# Telemetry_layoutmainVer3.net
KiCad netlist of a schematic drawn in EAGLE
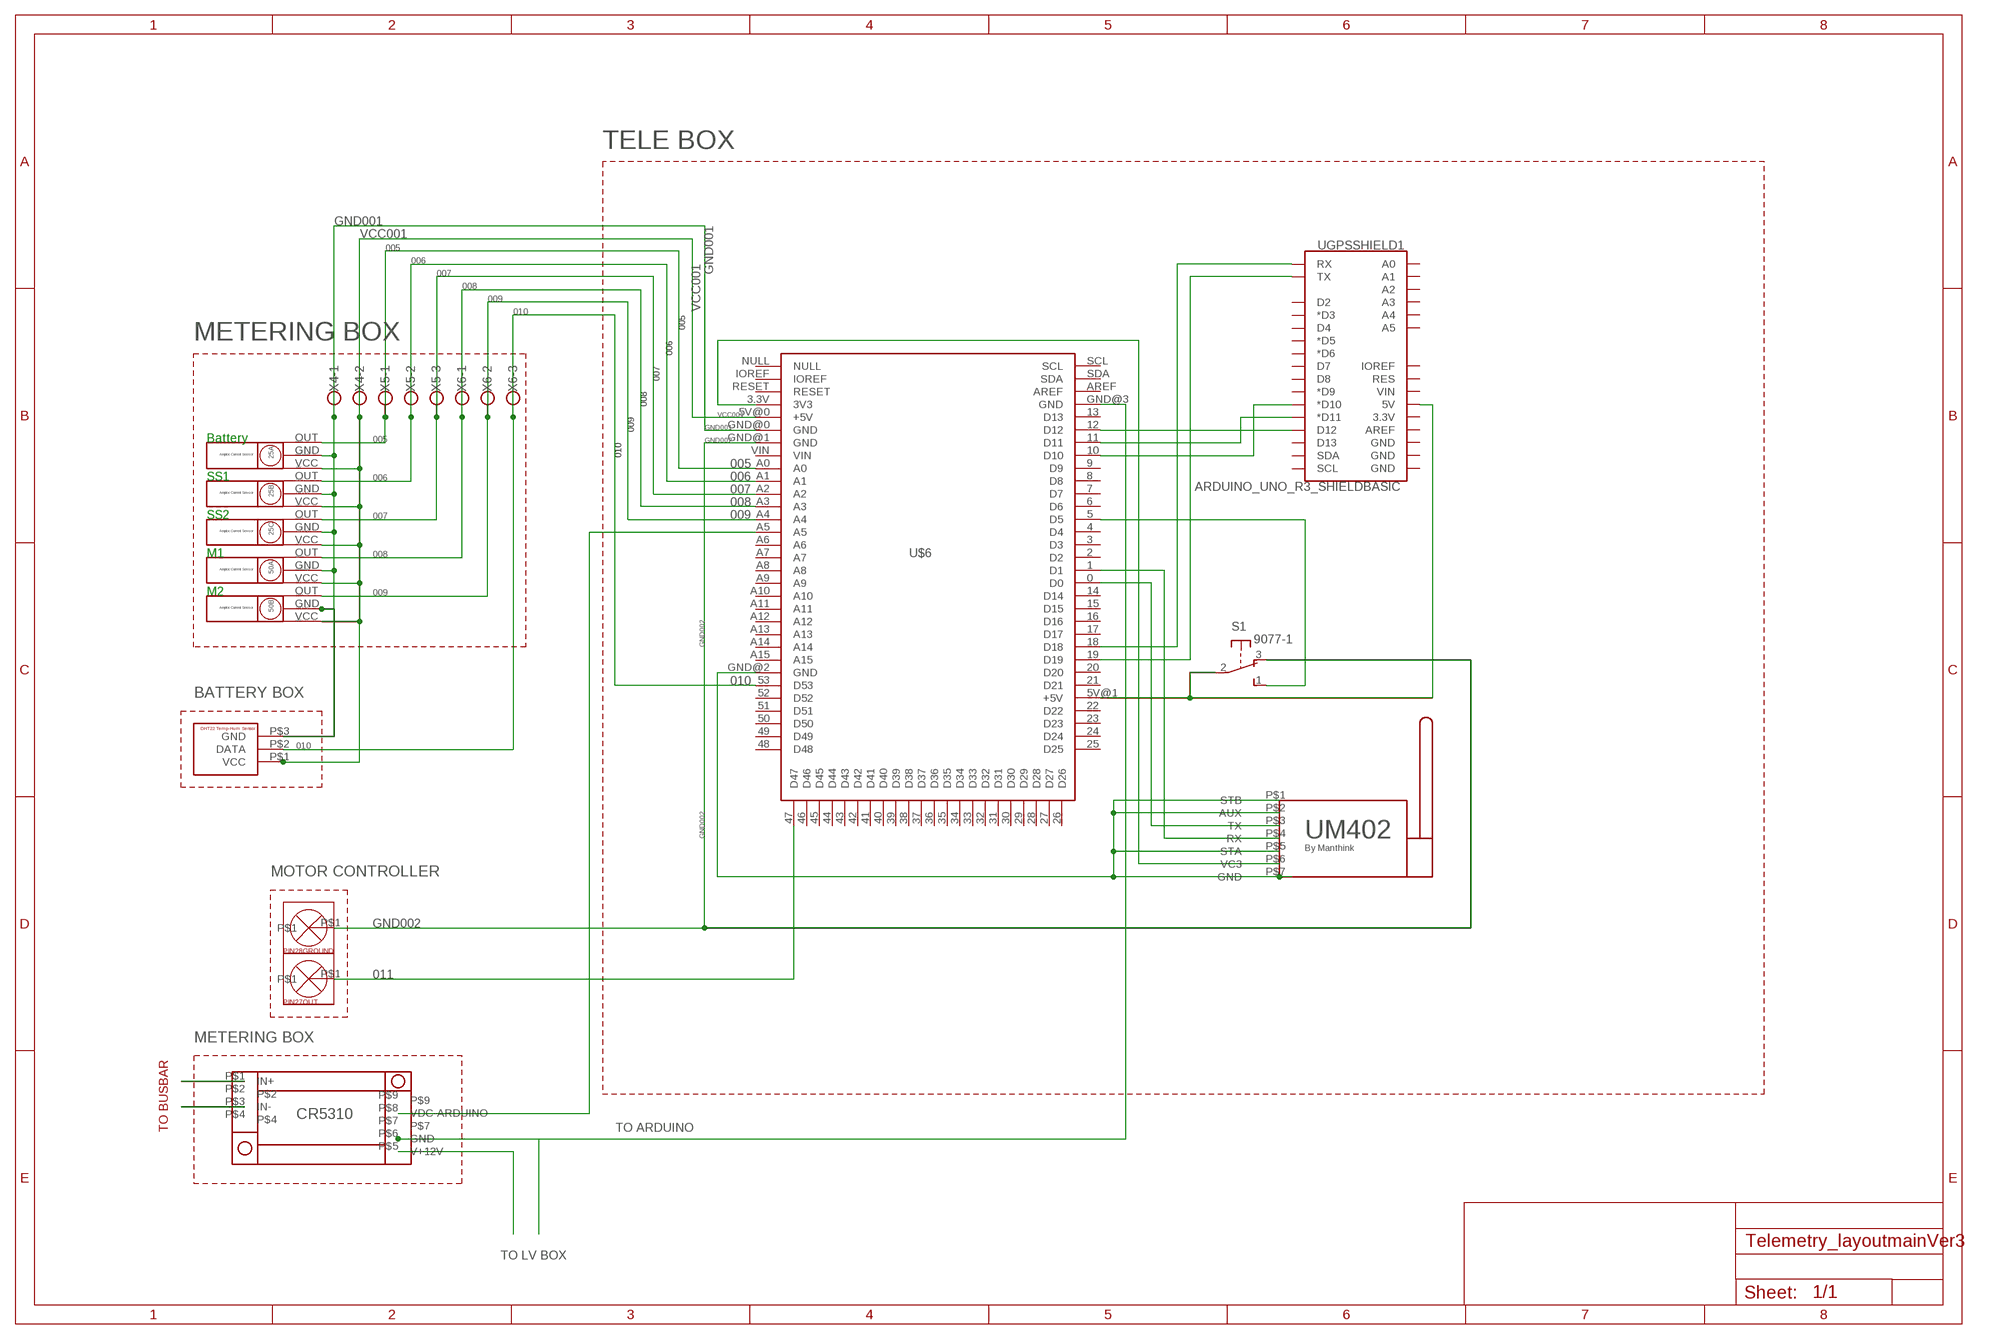
[diagram p0: schematic, sheet 1]

(export (version "E")
  (design (tool "Eeschema 10.0.6"))
  (components
    (comp (ref "25A")
      (value "AMPLOC-CS")
      (footprint "eagle-import:AMPLOC")
      (libsource (lib "eagle-import") (part "AMPLOC-CS"))
    )
    (comp (ref "25B")
      (value "AMPLOC-CS")
      (footprint "eagle-import:AMPLOC")
      (libsource (lib "eagle-import") (part "AMPLOC-CS"))
    )
    (comp (ref "25C")
      (value "AMPLOC-CS")
      (footprint "eagle-import:AMPLOC")
      (libsource (lib "eagle-import") (part "AMPLOC-CS"))
    )
    (comp (ref "50A")
      (value "AMPLOC-CS")
      (footprint "eagle-import:AMPLOC")
      (libsource (lib "eagle-import") (part "AMPLOC-CS"))
    )
    (comp (ref "50B")
      (value "AMPLOC-CS")
      (footprint "eagle-import:AMPLOC")
      (libsource (lib "eagle-import") (part "AMPLOC-CS"))
    )
    (comp (ref "PIN27OUT")
      (value "SCREWTERMINAL")
      (footprint "eagle-import:SCREWTERMINAL")
      (libsource (lib "eagle-import") (part "SCREWTERMINAL"))
    )
    (comp (ref "PIN28GROUND")
      (value "SCREWTERMINAL")
      (footprint "eagle-import:SCREWTERMINAL")
      (libsource (lib "eagle-import") (part "SCREWTERMINAL"))
    )
    (comp (ref "S1")
      (value "9077-1")
      (footprint "eagle-import:9077-1")
      (libsource (lib "eagle-import") (part "9077-1"))
    )
    (comp (ref "U$1")
      (value "CR5310")
      (footprint "eagle-import:CR5310")
      (libsource (lib "eagle-import") (part "CR5310"))
    )
    (comp (ref "U$2")
      (value "UM402")
      (footprint "eagle-import:UM402")
      (libsource (lib "eagle-import") (part "UM402"))
    )
    (comp (ref "U$6")
      (value "PSCREWBPROTOSCREWSHIELD")
      (footprint "eagle-import:ARDUINO_MEGA")
      (libsource (lib "eagle-import") (part "PSCREWBPROTOSCREWSHIELD"))
    )
    (comp (ref "U$8")
      (value "DHT22")
      (footprint "eagle-import:DHT22")
      (libsource (lib "eagle-import") (part "DHT22"))
    )
    (comp (ref "UGPSSHIELD1")
      (value "ARDUINO_UNO_R3_SHIELDBASIC")
      (footprint "eagle-import:UNO_R3_SHIELD")
      (libsource (lib "eagle-import") (part "ARDUINO_UNO_R3_SHIELDBASIC"))
    )
    (comp (ref "X4")
      (value "W237-102")
      (footprint "eagle-import:W237-102")
      (fields (field (name "MPN") "237-102"))
      (libsource (lib "eagle-import") (part "W237-102"))
    )
    (comp (ref "X5")
      (value "W237-103")
      (footprint "eagle-import:W237-103")
      (fields (field (name "MPN") "237-103"))
      (libsource (lib "eagle-import") (part "W237-103"))
    )
    (comp (ref "X6")
      (value "W237-103")
      (footprint "eagle-import:W237-103")
      (fields (field (name "MPN") "237-103"))
      (libsource (lib "eagle-import") (part "W237-103"))
    )
  )
  (nets
    (net (code "1") (name "Net-(25A-1)") (class "Default")
      (node (ref "25A") (pin "VCC") (pinfunction "1_VCC") (pintype "bidirectional"))
      (node (ref "25B") (pin "VCC") (pinfunction "1_VCC") (pintype "bidirectional"))
      (node (ref "25C") (pin "VCC") (pinfunction "1_VCC") (pintype "bidirectional"))
      (node (ref "50A") (pin "VCC") (pinfunction "1_VCC") (pintype "bidirectional"))
      (node (ref "50B") (pin "VCC") (pinfunction "1_VCC") (pintype "bidirectional"))
      (node (ref "U$6") (pin "5V@0") (pinfunction "+5V_5V@0") (pintype "bidirectional"))
      (node (ref "U$8") (pin "P$1") (pinfunction "VCC_P$1") (pintype "bidirectional"))
      (node (ref "X4") (pin "2") (pinfunction "KL_2") (pintype "passive"))
    )
    (net (code "2") (name "Net-(25A-2)") (class "Default")
      (node (ref "25A") (pin "GND") (pinfunction "2_GND") (pintype "bidirectional"))
      (node (ref "25B") (pin "GND") (pinfunction "2_GND") (pintype "bidirectional"))
      (node (ref "25C") (pin "GND") (pinfunction "2_GND") (pintype "bidirectional"))
      (node (ref "50A") (pin "GND") (pinfunction "2_GND") (pintype "bidirectional"))
      (node (ref "50B") (pin "GND") (pinfunction "2_GND") (pintype "bidirectional"))
      (node (ref "U$6") (pin "GND@0") (pinfunction "GND_GND@0") (pintype "bidirectional"))
      (node (ref "U$8") (pin "P$3") (pinfunction "GND_P$3") (pintype "bidirectional"))
      (node (ref "X4") (pin "1") (pinfunction "KL_1") (pintype "passive"))
    )
    (net (code "3") (name "Net-(25A-3)") (class "Default")
      (node (ref "25A") (pin "OUT") (pinfunction "3_OUT") (pintype "bidirectional"))
      (node (ref "U$6") (pin "A0") (pinfunction "A0_A0") (pintype "bidirectional"))
      (node (ref "X5") (pin "1") (pinfunction "KL_1") (pintype "passive"))
    )
    (net (code "4") (name "Net-(25B-3)") (class "Default")
      (node (ref "25B") (pin "OUT") (pinfunction "3_OUT") (pintype "bidirectional"))
      (node (ref "U$6") (pin "A1") (pinfunction "A1_A1") (pintype "bidirectional"))
      (node (ref "X5") (pin "2") (pinfunction "KL_2") (pintype "passive"))
    )
    (net (code "5") (name "Net-(25C-3)") (class "Default")
      (node (ref "25C") (pin "OUT") (pinfunction "3_OUT") (pintype "bidirectional"))
      (node (ref "U$6") (pin "A2") (pinfunction "A2_A2") (pintype "bidirectional"))
      (node (ref "X5") (pin "3") (pinfunction "KL_3") (pintype "passive"))
    )
    (net (code "6") (name "Net-(50A-3)") (class "Default")
      (node (ref "50A") (pin "OUT") (pinfunction "3_OUT") (pintype "bidirectional"))
      (node (ref "U$6") (pin "A3") (pinfunction "A3_A3") (pintype "bidirectional"))
      (node (ref "X6") (pin "1") (pinfunction "KL_1") (pintype "passive"))
    )
    (net (code "7") (name "Net-(50B-3)") (class "Default")
      (node (ref "50B") (pin "OUT") (pinfunction "3_OUT") (pintype "bidirectional"))
      (node (ref "U$6") (pin "A4") (pinfunction "A4_A4") (pintype "bidirectional"))
      (node (ref "X6") (pin "2") (pinfunction "KL_2") (pintype "passive"))
    )
    (net (code "8") (name "Net-(S1-O)") (class "Default")
      (node (ref "PIN28GROUND") (pin "P$1") (pinfunction "P$1_P$1") (pintype "bidirectional"))
      (node (ref "S1") (pin "3") (pinfunction "O_3") (pintype "passive"))
      (node (ref "U$6") (pin "GND@1") (pinfunction "GND_GND@1") (pintype "bidirectional"))
    )
    (net (code "9") (name "Net-(S1-P)") (class "Default")
      (node (ref "S1") (pin "2") (pinfunction "P_2") (pintype "passive"))
      (node (ref "U$6") (pin "5V@1") (pinfunction "+5V_5V@1") (pintype "bidirectional"))
      (node (ref "UGPSSHIELD1") (pin "5V") (pinfunction "5V_5V") (pintype "bidirectional"))
    )
    (net (code "10") (name "Net-(S1-S)") (class "Default")
      (node (ref "S1") (pin "1") (pinfunction "S_1") (pintype "passive"))
      (node (ref "U$6") (pin "5") (pinfunction "D5_5") (pintype "bidirectional"))
    )
    (net (code "11") (name "Net-(U$1-GND)") (class "Default")
      (node (ref "U$1") (pin "P$6") (pinfunction "GND_P$6") (pintype "bidirectional"))
      (node (ref "U$6") (pin "GND@3") (pinfunction "GND_GND@3") (pintype "bidirectional"))
    )
    (net (code "12") (name "Net-(U$1-VDC-ARDUINO)") (class "Default")
      (node (ref "U$1") (pin "P$8") (pinfunction "VDC-ARDUINO_P$8") (pintype "bidirectional"))
      (node (ref "U$6") (pin "A5") (pinfunction "A5_A5") (pintype "bidirectional"))
    )
    (net (code "13") (name "Net-(U$2-AUX)") (class "Default")
      (node (ref "U$2") (pin "P$1") (pinfunction "STB_P$1") (pintype "bidirectional"))
      (node (ref "U$2") (pin "P$2") (pinfunction "AUX_P$2") (pintype "bidirectional"))
      (node (ref "U$2") (pin "P$5") (pinfunction "STA_P$5") (pintype "bidirectional"))
      (node (ref "U$2") (pin "P$7") (pinfunction "GND_P$7") (pintype "bidirectional"))
      (node (ref "U$6") (pin "GND@2") (pinfunction "GND_GND@2") (pintype "bidirectional"))
    )
    (net (code "14") (name "Net-(U$2-RX)") (class "Default")
      (node (ref "U$2") (pin "P$4") (pinfunction "RX_P$4") (pintype "bidirectional"))
      (node (ref "U$6") (pin "1") (pinfunction "D1_1") (pintype "bidirectional"))
    )
    (net (code "15") (name "Net-(U$2-TX)") (class "Default")
      (node (ref "U$2") (pin "P$3") (pinfunction "TX_P$3") (pintype "bidirectional"))
      (node (ref "U$6") (pin "0") (pinfunction "D0_0") (pintype "bidirectional"))
    )
    (net (code "16") (name "Net-(U$2-VC3)") (class "Default")
      (node (ref "U$2") (pin "P$6") (pinfunction "VC3_P$6") (pintype "bidirectional"))
      (node (ref "U$6") (pin "3.3V") (pinfunction "3V3_3.3V") (pintype "bidirectional"))
    )
    (net (code "17") (name "Net-(U$6-D10)") (class "Default")
      (node (ref "U$6") (pin "10") (pinfunction "D10_10") (pintype "bidirectional"))
      (node (ref "UGPSSHIELD1") (pin "D10") (pinfunction "*D10_D10") (pintype "bidirectional"))
    )
    (net (code "18") (name "Net-(U$6-D11)") (class "Default")
      (node (ref "U$6") (pin "11") (pinfunction "D11_11") (pintype "bidirectional"))
      (node (ref "UGPSSHIELD1") (pin "D11") (pinfunction "*D11_D11") (pintype "bidirectional"))
    )
    (net (code "19") (name "Net-(U$6-D12)") (class "Default")
      (node (ref "U$6") (pin "12") (pinfunction "D12_12") (pintype "bidirectional"))
      (node (ref "UGPSSHIELD1") (pin "D12") (pinfunction "D12_D12") (pintype "bidirectional"))
    )
    (net (code "20") (name "Net-(U$6-D18)") (class "Default")
      (node (ref "U$6") (pin "18") (pinfunction "D18_18") (pintype "bidirectional"))
      (node (ref "UGPSSHIELD1") (pin "RX") (pinfunction "RX_RX") (pintype "bidirectional"))
    )
    (net (code "21") (name "Net-(U$6-D19)") (class "Default")
      (node (ref "U$6") (pin "19") (pinfunction "D19_19") (pintype "bidirectional"))
      (node (ref "UGPSSHIELD1") (pin "TX") (pinfunction "TX_TX") (pintype "bidirectional"))
    )
    (net (code "22") (name "Net-(U$6-D47)") (class "Default")
      (node (ref "PIN27OUT") (pin "P$1") (pinfunction "P$1_P$1") (pintype "bidirectional"))
      (node (ref "U$6") (pin "47") (pinfunction "D47_47") (pintype "bidirectional"))
    )
    (net (code "23") (name "Net-(U$6-D53)") (class "Default")
      (node (ref "U$6") (pin "53") (pinfunction "D53_53") (pintype "bidirectional"))
      (node (ref "U$8") (pin "P$2") (pinfunction "DATA_P$2") (pintype "bidirectional"))
      (node (ref "X6") (pin "3") (pinfunction "KL_3") (pintype "passive"))
    )
    (net (code "24") (name "unconnected-(U$1-IN+-PadP$1)") (class "Default")
      (node (ref "U$1") (pin "P$1") (pinfunction "IN+_P$1") (pintype "bidirectional"))
    )
    (net (code "25") (name "unconnected-(U$1-IN--PadP$3)") (class "Default")
      (node (ref "U$1") (pin "P$3") (pinfunction "IN-_P$3") (pintype "bidirectional"))
    )
    (net (code "26") (name "unconnected-(U$1-PadP$2)") (class "Default")
      (node (ref "U$1") (pin "P$2") (pinfunction "P$2_P$2") (pintype "bidirectional"))
    )
    (net (code "27") (name "unconnected-(U$1-PadP$4)") (class "Default")
      (node (ref "U$1") (pin "P$4") (pinfunction "P$4_P$4") (pintype "bidirectional"))
    )
    (net (code "28") (name "unconnected-(U$1-PadP$7)") (class "Default")
      (node (ref "U$1") (pin "P$7") (pinfunction "P$7_P$7") (pintype "bidirectional"))
    )
    (net (code "29") (name "unconnected-(U$1-PadP$9)") (class "Default")
      (node (ref "U$1") (pin "P$9") (pinfunction "P$9_P$9") (pintype "bidirectional"))
    )
    (net (code "30") (name "unconnected-(U$1-V+12V-PadP$5)") (class "Default")
      (node (ref "U$1") (pin "P$5") (pinfunction "V+12V_P$5") (pintype "bidirectional"))
    )
    (net (code "31") (name "unconnected-(U$6-D2-Pad2)") (class "Default")
      (node (ref "U$6") (pin "2") (pinfunction "D2_2") (pintype "bidirectional"))
    )
    (net (code "32") (name "unconnected-(U$6-D3-Pad3)") (class "Default")
      (node (ref "U$6") (pin "3") (pinfunction "D3_3") (pintype "bidirectional"))
    )
    (net (code "33") (name "unconnected-(U$6-D4-Pad4)") (class "Default")
      (node (ref "U$6") (pin "4") (pinfunction "D4_4") (pintype "bidirectional"))
    )
    (net (code "34") (name "unconnected-(U$6-D6-Pad6)") (class "Default")
      (node (ref "U$6") (pin "6") (pinfunction "D6_6") (pintype "bidirectional"))
    )
    (net (code "35") (name "unconnected-(U$6-D7-Pad7)") (class "Default")
      (node (ref "U$6") (pin "7") (pinfunction "D7_7") (pintype "bidirectional"))
    )
    (net (code "36") (name "unconnected-(U$6-D8-Pad8)") (class "Default")
      (node (ref "U$6") (pin "8") (pinfunction "D8_8") (pintype "bidirectional"))
    )
    (net (code "37") (name "unconnected-(U$6-D9-Pad9)") (class "Default")
      (node (ref "U$6") (pin "9") (pinfunction "D9_9") (pintype "bidirectional"))
    )
    (net (code "38") (name "unconnected-(U$6-D13-Pad13)") (class "Default")
      (node (ref "U$6") (pin "13") (pinfunction "D13_13") (pintype "bidirectional"))
    )
    (net (code "39") (name "unconnected-(U$6-D14-Pad14)") (class "Default")
      (node (ref "U$6") (pin "14") (pinfunction "D14_14") (pintype "bidirectional"))
    )
    (net (code "40") (name "unconnected-(U$6-D15-Pad15)") (class "Default")
      (node (ref "U$6") (pin "15") (pinfunction "D15_15") (pintype "bidirectional"))
    )
    (net (code "41") (name "unconnected-(U$6-D16-Pad16)") (class "Default")
      (node (ref "U$6") (pin "16") (pinfunction "D16_16") (pintype "bidirectional"))
    )
    (net (code "42") (name "unconnected-(U$6-D17-Pad17)") (class "Default")
      (node (ref "U$6") (pin "17") (pinfunction "D17_17") (pintype "bidirectional"))
    )
    (net (code "43") (name "unconnected-(U$6-D20-Pad20)") (class "Default")
      (node (ref "U$6") (pin "20") (pinfunction "D20_20") (pintype "bidirectional"))
    )
    (net (code "44") (name "unconnected-(U$6-D21-Pad21)") (class "Default")
      (node (ref "U$6") (pin "21") (pinfunction "D21_21") (pintype "bidirectional"))
    )
    (net (code "45") (name "unconnected-(U$6-D22-Pad22)") (class "Default")
      (node (ref "U$6") (pin "22") (pinfunction "D22_22") (pintype "bidirectional"))
    )
    (net (code "46") (name "unconnected-(U$6-D23-Pad23)") (class "Default")
      (node (ref "U$6") (pin "23") (pinfunction "D23_23") (pintype "bidirectional"))
    )
    (net (code "47") (name "unconnected-(U$6-D24-Pad24)") (class "Default")
      (node (ref "U$6") (pin "24") (pinfunction "D24_24") (pintype "bidirectional"))
    )
    (net (code "48") (name "unconnected-(U$6-D25-Pad25)") (class "Default")
      (node (ref "U$6") (pin "25") (pinfunction "D25_25") (pintype "bidirectional"))
    )
    (net (code "49") (name "unconnected-(U$6-D26-Pad26)") (class "Default")
      (node (ref "U$6") (pin "26") (pinfunction "D26_26") (pintype "bidirectional"))
    )
    (net (code "50") (name "unconnected-(U$6-D27-Pad27)") (class "Default")
      (node (ref "U$6") (pin "27") (pinfunction "D27_27") (pintype "bidirectional"))
    )
    (net (code "51") (name "unconnected-(U$6-D28-Pad28)") (class "Default")
      (node (ref "U$6") (pin "28") (pinfunction "D28_28") (pintype "bidirectional"))
    )
    (net (code "52") (name "unconnected-(U$6-D29-Pad29)") (class "Default")
      (node (ref "U$6") (pin "29") (pinfunction "D29_29") (pintype "bidirectional"))
    )
    (net (code "53") (name "unconnected-(U$6-D30-Pad30)") (class "Default")
      (node (ref "U$6") (pin "30") (pinfunction "D30_30") (pintype "bidirectional"))
    )
    (net (code "54") (name "unconnected-(U$6-D31-Pad31)") (class "Default")
      (node (ref "U$6") (pin "31") (pinfunction "D31_31") (pintype "bidirectional"))
    )
    (net (code "55") (name "unconnected-(U$6-D32-Pad32)") (class "Default")
      (node (ref "U$6") (pin "32") (pinfunction "D32_32") (pintype "bidirectional"))
    )
    (net (code "56") (name "unconnected-(U$6-D33-Pad33)") (class "Default")
      (node (ref "U$6") (pin "33") (pinfunction "D33_33") (pintype "bidirectional"))
    )
    (net (code "57") (name "unconnected-(U$6-D34-Pad34)") (class "Default")
      (node (ref "U$6") (pin "34") (pinfunction "D34_34") (pintype "bidirectional"))
    )
    (net (code "58") (name "unconnected-(U$6-D35-Pad35)") (class "Default")
      (node (ref "U$6") (pin "35") (pinfunction "D35_35") (pintype "bidirectional"))
    )
    (net (code "59") (name "unconnected-(U$6-D36-Pad36)") (class "Default")
      (node (ref "U$6") (pin "36") (pinfunction "D36_36") (pintype "bidirectional"))
    )
    (net (code "60") (name "unconnected-(U$6-D37-Pad37)") (class "Default")
      (node (ref "U$6") (pin "37") (pinfunction "D37_37") (pintype "bidirectional"))
    )
    (net (code "61") (name "unconnected-(U$6-D38-Pad38)") (class "Default")
      (node (ref "U$6") (pin "38") (pinfunction "D38_38") (pintype "bidirectional"))
    )
    (net (code "62") (name "unconnected-(U$6-D39-Pad39)") (class "Default")
      (node (ref "U$6") (pin "39") (pinfunction "D39_39") (pintype "bidirectional"))
    )
    (net (code "63") (name "unconnected-(U$6-D40-Pad40)") (class "Default")
      (node (ref "U$6") (pin "40") (pinfunction "D40_40") (pintype "bidirectional"))
    )
    (net (code "64") (name "unconnected-(U$6-D41-Pad41)") (class "Default")
      (node (ref "U$6") (pin "41") (pinfunction "D41_41") (pintype "bidirectional"))
    )
    (net (code "65") (name "unconnected-(U$6-D42-Pad42)") (class "Default")
      (node (ref "U$6") (pin "42") (pinfunction "D42_42") (pintype "bidirectional"))
    )
    (net (code "66") (name "unconnected-(U$6-D43-Pad43)") (class "Default")
      (node (ref "U$6") (pin "43") (pinfunction "D43_43") (pintype "bidirectional"))
    )
    (net (code "67") (name "unconnected-(U$6-D44-Pad44)") (class "Default")
      (node (ref "U$6") (pin "44") (pinfunction "D44_44") (pintype "bidirectional"))
    )
    (net (code "68") (name "unconnected-(U$6-D45-Pad45)") (class "Default")
      (node (ref "U$6") (pin "45") (pinfunction "D45_45") (pintype "bidirectional"))
    )
    (net (code "69") (name "unconnected-(U$6-D46-Pad46)") (class "Default")
      (node (ref "U$6") (pin "46") (pinfunction "D46_46") (pintype "bidirectional"))
    )
    (net (code "70") (name "unconnected-(U$6-D48-Pad48)") (class "Default")
      (node (ref "U$6") (pin "48") (pinfunction "D48_48") (pintype "bidirectional"))
    )
    (net (code "71") (name "unconnected-(U$6-D49-Pad49)") (class "Default")
      (node (ref "U$6") (pin "49") (pinfunction "D49_49") (pintype "bidirectional"))
    )
    (net (code "72") (name "unconnected-(U$6-D50-Pad50)") (class "Default")
      (node (ref "U$6") (pin "50") (pinfunction "D50_50") (pintype "bidirectional"))
    )
    (net (code "73") (name "unconnected-(U$6-D51-Pad51)") (class "Default")
      (node (ref "U$6") (pin "51") (pinfunction "D51_51") (pintype "bidirectional"))
    )
    (net (code "74") (name "unconnected-(U$6-D52-Pad52)") (class "Default")
      (node (ref "U$6") (pin "52") (pinfunction "D52_52") (pintype "bidirectional"))
    )
    (net (code "75") (name "unconnected-(U$6-PadA6)") (class "Default")
      (node (ref "U$6") (pin "A6") (pinfunction "A6_A6") (pintype "bidirectional"))
    )
    (net (code "76") (name "unconnected-(U$6-PadA7)") (class "Default")
      (node (ref "U$6") (pin "A7") (pinfunction "A7_A7") (pintype "bidirectional"))
    )
    (net (code "77") (name "unconnected-(U$6-PadA8)") (class "Default")
      (node (ref "U$6") (pin "A8") (pinfunction "A8_A8") (pintype "bidirectional"))
    )
    (net (code "78") (name "unconnected-(U$6-PadA9)") (class "Default")
      (node (ref "U$6") (pin "A9") (pinfunction "A9_A9") (pintype "bidirectional"))
    )
    (net (code "79") (name "unconnected-(U$6-PadA10)") (class "Default")
      (node (ref "U$6") (pin "A10") (pinfunction "A10_A10") (pintype "bidirectional"))
    )
    (net (code "80") (name "unconnected-(U$6-PadA11)") (class "Default")
      (node (ref "U$6") (pin "A11") (pinfunction "A11_A11") (pintype "bidirectional"))
    )
    (net (code "81") (name "unconnected-(U$6-PadA12)") (class "Default")
      (node (ref "U$6") (pin "A12") (pinfunction "A12_A12") (pintype "bidirectional"))
    )
    (net (code "82") (name "unconnected-(U$6-PadA13)") (class "Default")
      (node (ref "U$6") (pin "A13") (pinfunction "A13_A13") (pintype "bidirectional"))
    )
    (net (code "83") (name "unconnected-(U$6-PadA14)") (class "Default")
      (node (ref "U$6") (pin "A14") (pinfunction "A14_A14") (pintype "bidirectional"))
    )
    (net (code "84") (name "unconnected-(U$6-PadA15)") (class "Default")
      (node (ref "U$6") (pin "A15") (pinfunction "A15_A15") (pintype "bidirectional"))
    )
    (net (code "85") (name "unconnected-(U$6-PadAREF)") (class "Default")
      (node (ref "U$6") (pin "AREF") (pinfunction "AREF_AREF") (pintype "bidirectional"))
    )
    (net (code "86") (name "unconnected-(U$6-PadIOREF)") (class "Default")
      (node (ref "U$6") (pin "IOREF") (pinfunction "IOREF_IOREF") (pintype "bidirectional"))
    )
    (net (code "87") (name "unconnected-(U$6-PadNULL)") (class "Default")
      (node (ref "U$6") (pin "NULL") (pinfunction "NULL_NULL") (pintype "bidirectional"))
    )
    (net (code "88") (name "unconnected-(U$6-PadRESET)") (class "Default")
      (node (ref "U$6") (pin "RESET") (pinfunction "RESET_RESET") (pintype "bidirectional"))
    )
    (net (code "89") (name "unconnected-(U$6-PadSCL)") (class "Default")
      (node (ref "U$6") (pin "SCL") (pinfunction "SCL_SCL") (pintype "bidirectional"))
    )
    (net (code "90") (name "unconnected-(U$6-PadSDA)") (class "Default")
      (node (ref "U$6") (pin "SDA") (pinfunction "SDA_SDA") (pintype "bidirectional"))
    )
    (net (code "91") (name "unconnected-(U$6-PadVIN)") (class "Default")
      (node (ref "U$6") (pin "VIN") (pinfunction "VIN_VIN") (pintype "bidirectional"))
    )
    (net (code "92") (name "unconnected-(UGPSSHIELD1-*D3-PadD3)") (class "Default")
      (node (ref "UGPSSHIELD1") (pin "D3") (pinfunction "*D3_D3") (pintype "bidirectional"))
    )
    (net (code "93") (name "unconnected-(UGPSSHIELD1-*D5-PadD5)") (class "Default")
      (node (ref "UGPSSHIELD1") (pin "D5") (pinfunction "*D5_D5") (pintype "bidirectional"))
    )
    (net (code "94") (name "unconnected-(UGPSSHIELD1-*D6-PadD6)") (class "Default")
      (node (ref "UGPSSHIELD1") (pin "D6") (pinfunction "*D6_D6") (pintype "bidirectional"))
    )
    (net (code "95") (name "unconnected-(UGPSSHIELD1-*D9-PadD9)") (class "Default")
      (node (ref "UGPSSHIELD1") (pin "D9") (pinfunction "*D9_D9") (pintype "bidirectional"))
    )
    (net (code "96") (name "unconnected-(UGPSSHIELD1-GND-PadGND@0)") (class "Default")
      (node (ref "UGPSSHIELD1") (pin "GND@0") (pinfunction "GND_GND@0") (pintype "bidirectional"))
    )
    (net (code "97") (name "unconnected-(UGPSSHIELD1-GND-PadGND@1)") (class "Default")
      (node (ref "UGPSSHIELD1") (pin "GND@1") (pinfunction "GND_GND@1") (pintype "bidirectional"))
    )
    (net (code "98") (name "unconnected-(UGPSSHIELD1-GND-PadGND@2)") (class "Default")
      (node (ref "UGPSSHIELD1") (pin "GND@2") (pinfunction "GND_GND@2") (pintype "bidirectional"))
    )
    (net (code "99") (name "unconnected-(UGPSSHIELD1-Pad3.3V)") (class "Default")
      (node (ref "UGPSSHIELD1") (pin "3.3V") (pinfunction "3.3V_3.3V") (pintype "bidirectional"))
    )
    (net (code "100") (name "unconnected-(UGPSSHIELD1-PadA0)") (class "Default")
      (node (ref "UGPSSHIELD1") (pin "A0") (pinfunction "A0_A0") (pintype "bidirectional"))
    )
    (net (code "101") (name "unconnected-(UGPSSHIELD1-PadA1)") (class "Default")
      (node (ref "UGPSSHIELD1") (pin "A1") (pinfunction "A1_A1") (pintype "bidirectional"))
    )
    (net (code "102") (name "unconnected-(UGPSSHIELD1-PadA2)") (class "Default")
      (node (ref "UGPSSHIELD1") (pin "A2") (pinfunction "A2_A2") (pintype "bidirectional"))
    )
    (net (code "103") (name "unconnected-(UGPSSHIELD1-PadA3)") (class "Default")
      (node (ref "UGPSSHIELD1") (pin "A3") (pinfunction "A3_A3") (pintype "bidirectional"))
    )
    (net (code "104") (name "unconnected-(UGPSSHIELD1-PadA4)") (class "Default")
      (node (ref "UGPSSHIELD1") (pin "A4") (pinfunction "A4_A4") (pintype "bidirectional"))
    )
    (net (code "105") (name "unconnected-(UGPSSHIELD1-PadA5)") (class "Default")
      (node (ref "UGPSSHIELD1") (pin "A5") (pinfunction "A5_A5") (pintype "bidirectional"))
    )
    (net (code "106") (name "unconnected-(UGPSSHIELD1-PadAREF)") (class "Default")
      (node (ref "UGPSSHIELD1") (pin "AREF") (pinfunction "AREF_AREF") (pintype "bidirectional"))
    )
    (net (code "107") (name "unconnected-(UGPSSHIELD1-PadD2)") (class "Default")
      (node (ref "UGPSSHIELD1") (pin "D2") (pinfunction "D2_D2") (pintype "bidirectional"))
    )
    (net (code "108") (name "unconnected-(UGPSSHIELD1-PadD4)") (class "Default")
      (node (ref "UGPSSHIELD1") (pin "D4") (pinfunction "D4_D4") (pintype "bidirectional"))
    )
    (net (code "109") (name "unconnected-(UGPSSHIELD1-PadD7)") (class "Default")
      (node (ref "UGPSSHIELD1") (pin "D7") (pinfunction "D7_D7") (pintype "bidirectional"))
    )
    (net (code "110") (name "unconnected-(UGPSSHIELD1-PadD8)") (class "Default")
      (node (ref "UGPSSHIELD1") (pin "D8") (pinfunction "D8_D8") (pintype "bidirectional"))
    )
    (net (code "111") (name "unconnected-(UGPSSHIELD1-PadD13)") (class "Default")
      (node (ref "UGPSSHIELD1") (pin "D13") (pinfunction "D13_D13") (pintype "bidirectional"))
    )
    (net (code "112") (name "unconnected-(UGPSSHIELD1-PadIOREF)") (class "Default")
      (node (ref "UGPSSHIELD1") (pin "IOREF") (pinfunction "IOREF_IOREF") (pintype "bidirectional"))
    )
    (net (code "113") (name "unconnected-(UGPSSHIELD1-PadRES)") (class "Default")
      (node (ref "UGPSSHIELD1") (pin "RES") (pinfunction "RES_RES") (pintype "bidirectional"))
    )
    (net (code "114") (name "unconnected-(UGPSSHIELD1-PadSCL)") (class "Default")
      (node (ref "UGPSSHIELD1") (pin "SCL") (pinfunction "SCL_SCL") (pintype "bidirectional"))
    )
    (net (code "115") (name "unconnected-(UGPSSHIELD1-PadSDA)") (class "Default")
      (node (ref "UGPSSHIELD1") (pin "SDA") (pinfunction "SDA_SDA") (pintype "bidirectional"))
    )
    (net (code "116") (name "unconnected-(UGPSSHIELD1-PadVIN)") (class "Default")
      (node (ref "UGPSSHIELD1") (pin "VIN") (pinfunction "VIN_VIN") (pintype "bidirectional"))
    )
  )
)
